# SerialCommunication2.net
KiCad netlist of a schematic drawn in Altium Designer
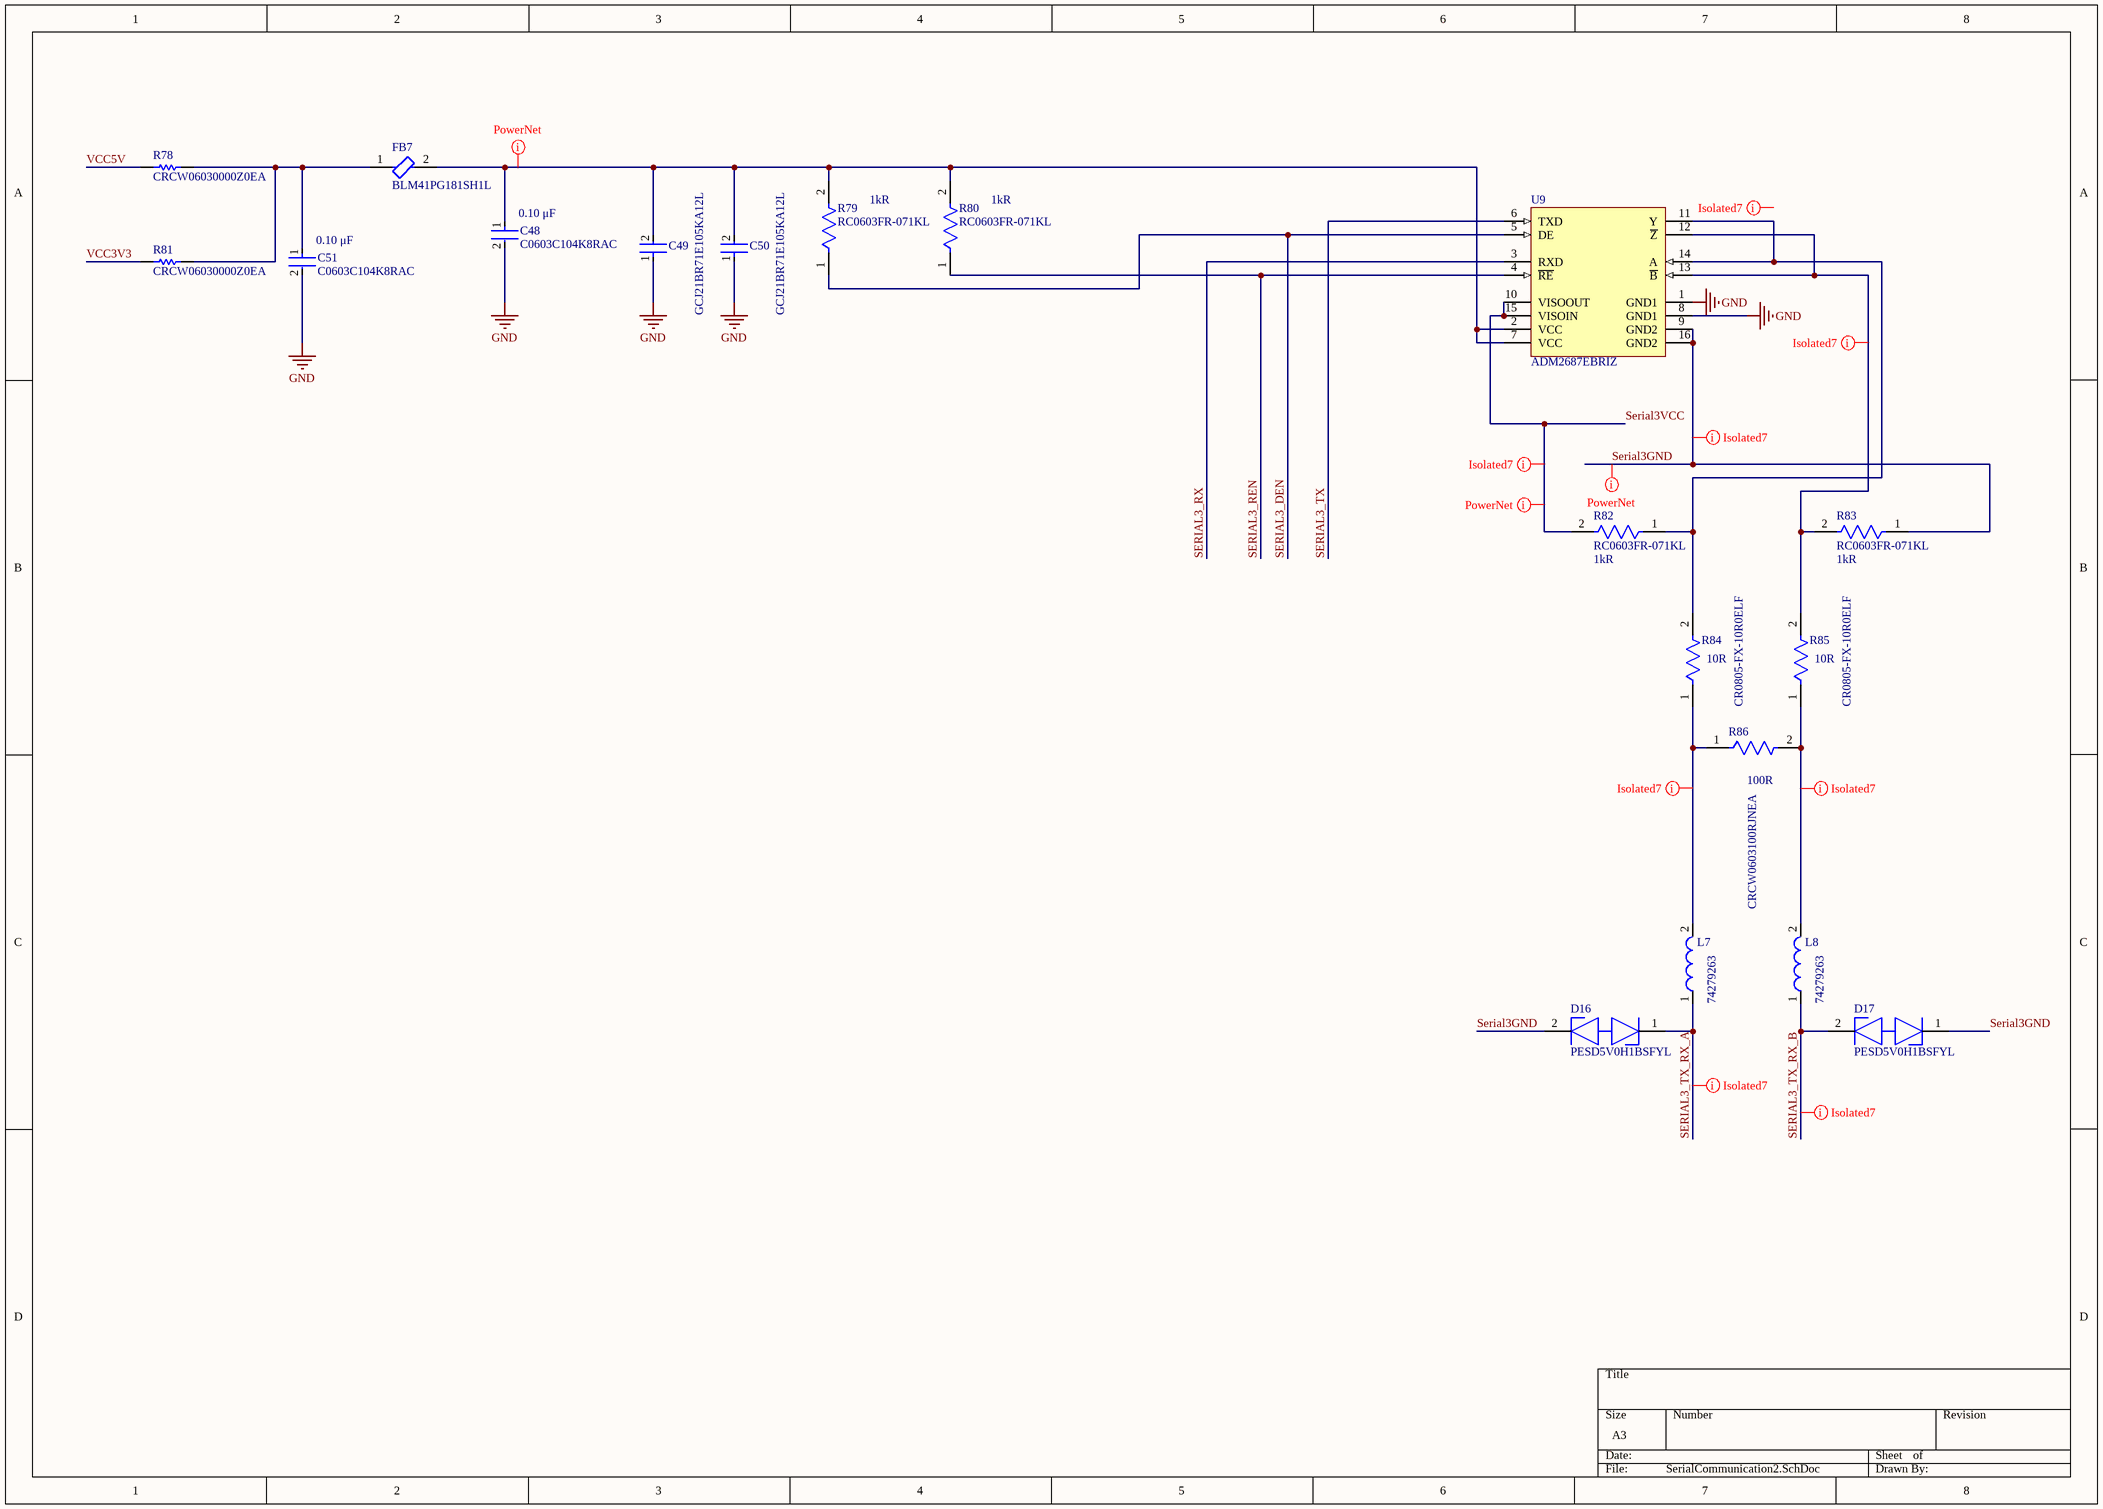
[diagram p0: SerialCommunication2.SchDoc]

(export (version "E")
  (design (tool "Eeschema 10.0.6"))
  (components
    (comp (ref "C48")
      (value "C0603C104K8RAC")
      (footprint "FP-C0603C-CF-MFG")
      (description "C0603 0.10 μF X7R 30ppm/°C 10.00% 10 V")
      (fields
        (field (name "MANUFACTURER") "KEMET")
        (field (name "CAPACITANCE") "0.10 μF")
        (field (name "OCTOPART") "https://octopart.com/c0603c104k8rac-kemet-1325403")
      )
      (libsource (lib "Altium Content Vault") (part "b4654b650e69147ec39a6b967a45e02"))
    )
    (comp (ref "C49")
      (value "GCJ21BR71E105KA12L")
      (footprint "FP-GCJ21B-0_3-MFG")
      (description "Multilayer Ceramic Capacitors MLCC - SMD/SMT 0805 1uF 10%, 25VDC,  X7R 15%")
      (fields (field (name "TOLERANCE") "10%"))
      (libsource (lib "Altium Content Vault") (part "02cd4be3c70576c341d710602a673aa"))
    )
    (comp (ref "C50")
      (value "GCJ21BR71E105KA12L")
      (footprint "FP-GCJ21B-0_3-MFG")
      (description "Multilayer Ceramic Capacitors MLCC - SMD/SMT 0805 1uF 10%, 25VDC,  X7R 15%")
      (fields (field (name "TOLERANCE") "10%"))
      (libsource (lib "Altium Content Vault") (part "02cd4be3c70576c341d710602a673aa"))
    )
    (comp (ref "C51")
      (value "C0603C104K8RAC")
      (footprint "FP-C0603C-CF-MFG")
      (description "C0603 0.10 μF X7R 30ppm/°C 10.00% 10 V")
      (fields
        (field (name "MANUFACTURER") "KEMET")
        (field (name "CAPACITANCE") "0.10 μF")
        (field (name "OCTOPART") "https://octopart.com/c0603c104k8rac-kemet-1325403")
      )
      (libsource (lib "Altium Content Vault") (part "b4654b650e69147ec39a6b967a45e02"))
    )
    (comp (ref "D16")
      (value "PESD5V0H1BSFYL")
      (footprint "FP-SOD962-2-MFG")
      (description "TVS DIODE 5V 5V DSN0603-2")
      (fields
        (field (name "OCTOPART") "https://octopart.com/pesd5v0h1bsfyl-nexperia-78741149")
        (field (name "MANUFACTURER") "Nexperia")
      )
      (libsource (lib "Altium Content Vault") (part "35d3c4067516f6c39e60198d779250f"))
    )
    (comp (ref "D17")
      (value "PESD5V0H1BSFYL")
      (footprint "FP-SOD962-2-MFG")
      (description "TVS DIODE 5V 5V DSN0603-2")
      (fields
        (field (name "OCTOPART") "https://octopart.com/pesd5v0h1bsfyl-nexperia-78741149")
        (field (name "MANUFACTURER") "Nexperia")
      )
      (libsource (lib "Altium Content Vault") (part "35d3c4067516f6c39e60198d779250f"))
    )
    (comp (ref "FB7")
      (value "BLM41PG181SH1L")
      (footprint "FP-BLM41-0_2-a1_2-MFG")
      (description "Ferrite Bead, 1806, 180Ω @ 100MHz, 25%, 0.02Ω, 3.5A")
      (fields (field (name "TOLERANCE") "25%"))
      (libsource (lib "Altium Content Vault") (part "5f30dd21d616792df468990f7003faa"))
    )
    (comp (ref "L7")
      (value "74279263")
      (footprint "SMD-0603")
      (description "SMD EMI Suppression Ferrite Bead WE-CBF, Z = 220 Ohm")
      (libsource (lib "Altium Content Vault") (part "PAS-IND-INDUCTOR-2"))
    )
    (comp (ref "L8")
      (value "74279263")
      (footprint "SMD-0603")
      (description "SMD EMI Suppression Ferrite Bead WE-CBF, Z = 220 Ohm")
      (libsource (lib "Altium Content Vault") (part "PAS-IND-INDUCTOR-2"))
    )
    (comp (ref "R78")
      (value "CRCW06030000Z0EA")
      (footprint "RESC1609X50X30NL8T20")
      (description "Chip Resistor, 0 Ohm, Jumper, 100 mW, -55 to 155 degC, 0603 (1608 Metric), RoHS, Tape and Reel")
      (fields (field (name "MANUFACTURER") "Vishay Semiconductor"))
      (libsource (lib "Altium Content Vault") (part "RES-2"))
    )
    (comp (ref "R79")
      (value "RC0603FR-071KL")
      (footprint "FP-RC0603-0_55-IPC_C")
      (description "RES 1K OHM 1% 1/10W 0603")
      (fields (field (name "RESISTANCE") "1kR") (field (name "TOLERANCE") "1%"))
      (libsource (lib "Altium Content Vault") (part "1029c3af85768c4190bb7ad29bc67b5"))
    )
    (comp (ref "R80")
      (value "RC0603FR-071KL")
      (footprint "FP-RC0603-0_55-IPC_C")
      (description "RES 1K OHM 1% 1/10W 0603")
      (fields (field (name "RESISTANCE") "1kR") (field (name "TOLERANCE") "1%"))
      (libsource (lib "Altium Content Vault") (part "1029c3af85768c4190bb7ad29bc67b5"))
    )
    (comp (ref "R81")
      (value "CRCW06030000Z0EA")
      (footprint "RESC1609X50X30NL8T20")
      (description "Chip Resistor, 0 Ohm, Jumper, 100 mW, -55 to 155 degC, 0603 (1608 Metric), RoHS, Tape and Reel")
      (fields (field (name "MANUFACTURER") "Vishay Semiconductor"))
      (libsource (lib "Altium Content Vault") (part "RES-2"))
    )
    (comp (ref "R82")
      (value "RC0603FR-071KL")
      (footprint "FP-RC0603-0_55-IPC_C")
      (description "RES 1K OHM 1% 1/10W 0603")
      (fields (field (name "RESISTANCE") "1kR") (field (name "TOLERANCE") "1%"))
      (libsource (lib "Altium Content Vault") (part "1029c3af85768c4190bb7ad29bc67b5"))
    )
    (comp (ref "R83")
      (value "RC0603FR-071KL")
      (footprint "FP-RC0603-0_55-IPC_C")
      (description "RES 1K OHM 1% 1/10W 0603")
      (fields (field (name "RESISTANCE") "1kR") (field (name "TOLERANCE") "1%"))
      (libsource (lib "Altium Content Vault") (part "1029c3af85768c4190bb7ad29bc67b5"))
    )
    (comp (ref "R84")
      (value "CR0805-FX-10R0ELF")
      (footprint "FP-CR0805-IPC_B")
      (description "Thick Film Chip Resistors 0805 10Ω 0.125W 1% 100ppm/°C")
      (fields (field (name "TOLERANCE") "1%") (field (name "RESISTANCE") "10R"))
      (libsource (lib "Altium Content Vault") (part "1029c3af85768c4190bb7ad29bc67b5"))
    )
    (comp (ref "R85")
      (value "CR0805-FX-10R0ELF")
      (footprint "FP-CR0805-IPC_B")
      (description "Thick Film Chip Resistors 0805 10Ω 0.125W 1% 100ppm/°C")
      (fields (field (name "TOLERANCE") "1%") (field (name "RESISTANCE") "10R"))
      (libsource (lib "Altium Content Vault") (part "1029c3af85768c4190bb7ad29bc67b5"))
    )
    (comp (ref "R86")
      (value "CRCW0603100RJNEA")
      (footprint "FP-CRCW0603-e3-IPC_B")
      (description "RES Thick Film, 100Ω, 5%, 0.1W, 200ppm/°C, 0603")
      (fields (field (name "RESISTANCE") "100R") (field (name "TOLERANCE") "5%"))
      (libsource (lib "Altium Content Vault") (part "1029c3af85768c4190bb7ad29bc67b5"))
    )
    (comp (ref "U9")
      (value "ADM2687EBRIZ")
      (footprint "ADI-RI-16-2_L")
      (fields (field (name "MANUFACTURER") "Analog Devices"))
      (libsource (lib "Altium Content Vault") (part "ADI-ADM268X-RI-16-2"))
    )
  )
  (nets
    (net (code "1") (name "/SERIAL3_DEN") (class "Default")
      (node (ref "R79") (pin "1") (pinfunction "1_1") (pintype "passive"))
      (node (ref "U9") (pin "5") (pinfunction "DE_5") (pintype "input"))
    )
    (net (code "2") (name "/SERIAL3_REN") (class "Default")
      (node (ref "R80") (pin "1") (pinfunction "1_1") (pintype "passive"))
      (node (ref "U9") (pin "4") (pinfunction "~{RE}_4") (pintype "input"))
    )
    (net (code "3") (name "/SERIAL3_RX") (class "Default")
      (node (ref "U9") (pin "3") (pinfunction "RXD_3") (pintype "tri_state"))
    )
    (net (code "4") (name "/SERIAL3_TX") (class "Default")
      (node (ref "U9") (pin "6") (pinfunction "TXD_6") (pintype "input"))
    )
    (net (code "5") (name "/SERIAL3_TX_RX_A") (class "Default")
      (node (ref "D16") (pin "1") (pinfunction "K1_1") (pintype "passive"))
      (node (ref "L7") (pin "1") (pinfunction "1_1") (pintype "passive"))
    )
    (net (code "6") (name "/SERIAL3_TX_RX_B") (class "Default")
      (node (ref "D17") (pin "2") (pinfunction "K2_2") (pintype "passive"))
      (node (ref "L8") (pin "1") (pinfunction "1_1") (pintype "passive"))
    )
    (net (code "7") (name "/Serial3GND") (class "Default")
      (node (ref "D16") (pin "2") (pinfunction "K2_2") (pintype "passive"))
      (node (ref "D17") (pin "1") (pinfunction "K1_1") (pintype "passive"))
      (node (ref "R83") (pin "1") (pinfunction "1_1") (pintype "passive"))
      (node (ref "U9") (pin "16") (pinfunction "GND2_16") (pintype "power_in"))
      (node (ref "U9") (pin "9") (pinfunction "GND2_9") (pintype "power_in"))
    )
    (net (code "8") (name "/Serial3VCC") (class "Default")
      (node (ref "R82") (pin "2") (pinfunction "2_2") (pintype "passive"))
      (node (ref "U9") (pin "10") (pinfunction "VISOOUT_10") (pintype "power_in"))
      (node (ref "U9") (pin "15") (pinfunction "VISOIN_15") (pintype "power_in"))
    )
    (net (code "9") (name "/VCC3V3") (class "Default")
      (node (ref "R81") (pin "1") (pinfunction "1_1") (pintype "passive"))
    )
    (net (code "10") (name "/VCC5V") (class "Default")
      (node (ref "R78") (pin "1") (pinfunction "1_1") (pintype "passive"))
    )
    (net (code "11") (name "GND") (class "Default")
      (node (ref "C48") (pin "2") (pinfunction "2_2") (pintype "passive"))
      (node (ref "C49") (pin "1") (pinfunction "1_1") (pintype "passive"))
      (node (ref "C50") (pin "1") (pinfunction "1_1") (pintype "passive"))
      (node (ref "C51") (pin "2") (pinfunction "2_2") (pintype "passive"))
      (node (ref "U9") (pin "1") (pinfunction "GND1_1") (pintype "power_in"))
      (node (ref "U9") (pin "8") (pinfunction "GND1_8") (pintype "power_in"))
    )
    (net (code "12") (name "Net-(C48-Pad1)") (class "Default")
      (node (ref "C48") (pin "1") (pinfunction "1_1") (pintype "passive"))
      (node (ref "C49") (pin "2") (pinfunction "2_2") (pintype "passive"))
      (node (ref "C50") (pin "2") (pinfunction "2_2") (pintype "passive"))
      (node (ref "FB7") (pin "2") (pinfunction "2_2") (pintype "passive"))
      (node (ref "R79") (pin "2") (pinfunction "2_2") (pintype "passive"))
      (node (ref "R80") (pin "2") (pinfunction "2_2") (pintype "passive"))
      (node (ref "U9") (pin "2") (pinfunction "VCC_2") (pintype "power_in"))
      (node (ref "U9") (pin "7") (pinfunction "VCC_7") (pintype "power_in"))
    )
    (net (code "13") (name "Net-(C51-Pad1)") (class "Default")
      (node (ref "C51") (pin "1") (pinfunction "1_1") (pintype "passive"))
      (node (ref "FB7") (pin "1") (pinfunction "1_1") (pintype "passive"))
      (node (ref "R78") (pin "2") (pinfunction "2_2") (pintype "passive"))
      (node (ref "R81") (pin "2") (pinfunction "2_2") (pintype "passive"))
    )
    (net (code "14") (name "Net-(L7-Pad2)") (class "Default")
      (node (ref "L7") (pin "2") (pinfunction "2_2") (pintype "passive"))
      (node (ref "R84") (pin "1") (pinfunction "1_1") (pintype "passive"))
      (node (ref "R86") (pin "1") (pinfunction "1_1") (pintype "passive"))
    )
    (net (code "15") (name "Net-(L8-Pad2)") (class "Default")
      (node (ref "L8") (pin "2") (pinfunction "2_2") (pintype "passive"))
      (node (ref "R85") (pin "1") (pinfunction "1_1") (pintype "passive"))
      (node (ref "R86") (pin "2") (pinfunction "2_2") (pintype "passive"))
    )
    (net (code "16") (name "Net-(U9-A)") (class "Default")
      (node (ref "R82") (pin "1") (pinfunction "1_1") (pintype "passive"))
      (node (ref "R84") (pin "2") (pinfunction "2_2") (pintype "passive"))
      (node (ref "U9") (pin "11") (pinfunction "Y_11") (pintype "tri_state"))
      (node (ref "U9") (pin "14") (pinfunction "A_14") (pintype "input"))
    )
    (net (code "17") (name "Net-(U9-~{B})") (class "Default")
      (node (ref "R83") (pin "2") (pinfunction "2_2") (pintype "passive"))
      (node (ref "R85") (pin "2") (pinfunction "2_2") (pintype "passive"))
      (node (ref "U9") (pin "12") (pinfunction "~{Z}_12") (pintype "tri_state"))
      (node (ref "U9") (pin "13") (pinfunction "~{B}_13") (pintype "input"))
    )
  )
)
